# 1-Schematic_AU9560-SC-Reader.net
KiCad netlist of a schematic drawn in EasyEDA
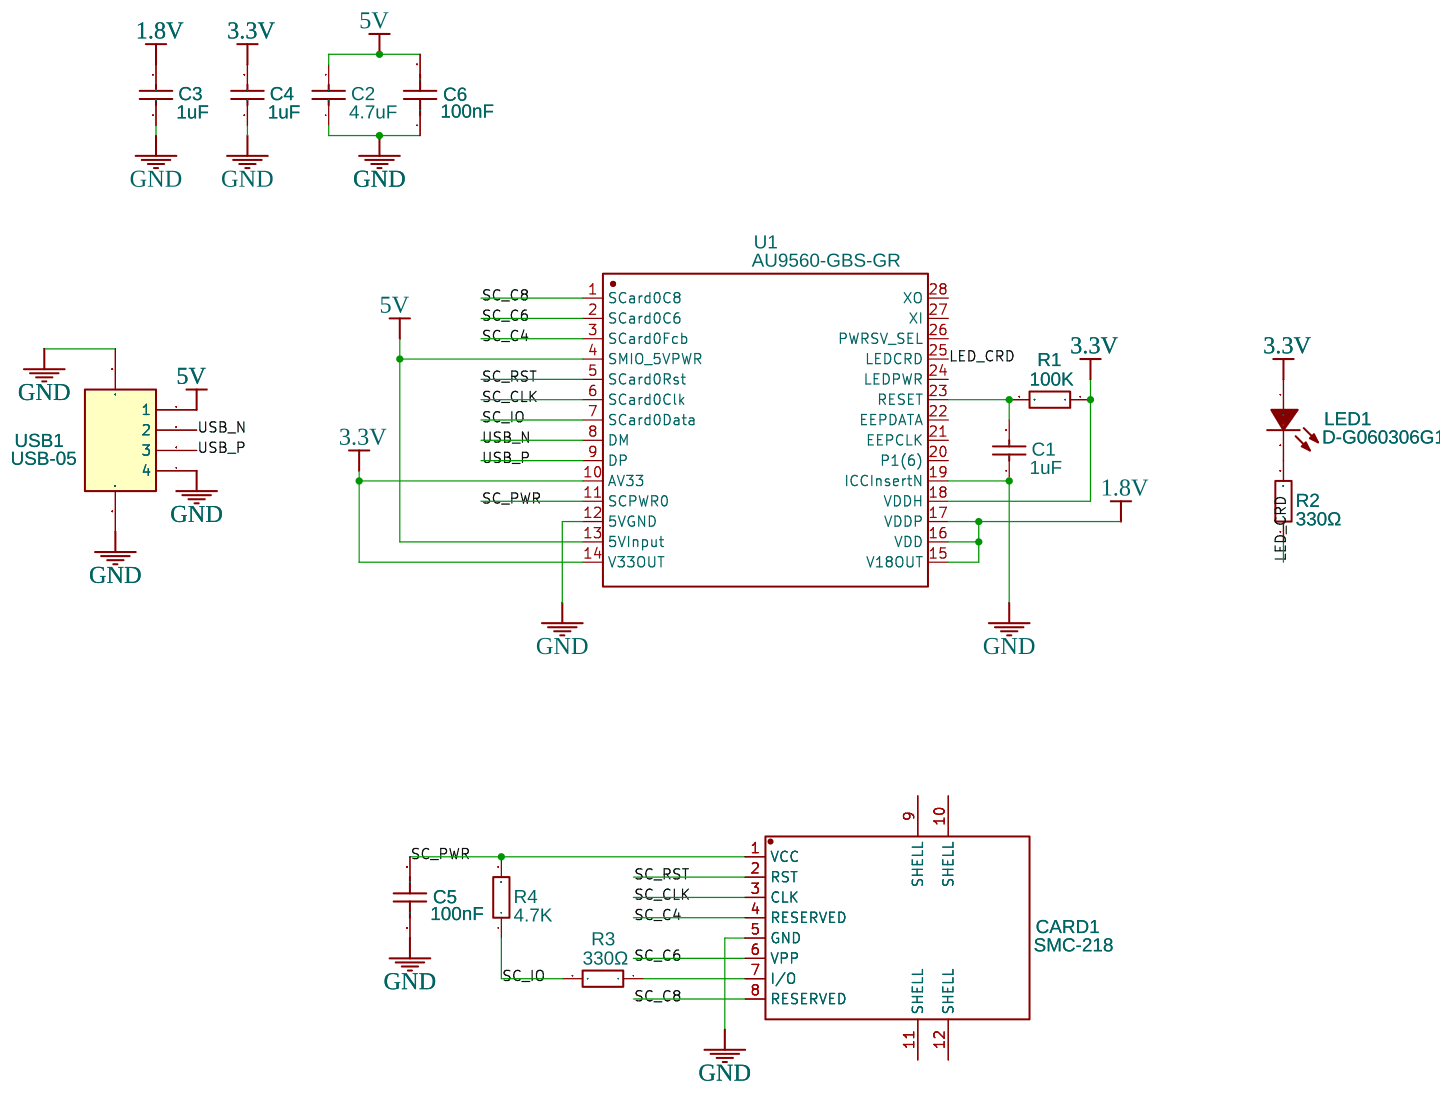
[diagram p0: schematic sheet]

(export (version "E")
  (design (tool "Eeschema 10.0.6"))
  (components
    (comp (ref "C1") (value "1uF") (libsource (lib "") (part "CL10A475KO8NNNC")))
    (comp (ref "C2") (value "4.7uF") (libsource (lib "") (part "CL10A475KO8NNNC")))
    (comp (ref "C3") (value "1uF") (libsource (lib "") (part "CL10A475KO8NNNC")))
    (comp (ref "C4") (value "1uF") (libsource (lib "") (part "CL10A475KO8NNNC")))
    (comp (ref "C5") (value "100nF") (libsource (lib "") (part "CC0603KRX7R9BB104")))
    (comp (ref "C6") (value "100nF") (libsource (lib "") (part "CC0603KRX7R9BB104")))
    (comp (ref "CARD1")
      (value "SMC-218")
      (fields (field (name "BOM_Supplier Part") "C266885"))
      (libsource (lib "") (part "Unknown_60_255"))
    )
    (comp (ref "LED1")
      (value "D-G060306G1-KS2")
      (fields (field (name "BOM_Supplier Part") "C118334"))
      (libsource (lib "") (part "Unknown_255_5"))
    )
    (comp (ref "R1") (value "100K") (libsource (lib "") (part "TC0325B1002T5E")))
    (comp (ref "R2") (value "330Ω") (libsource (lib "") (part "TC0350F4701T5E_C179829")))
    (comp (ref "R3") (value "330Ω") (libsource (lib "") (part "0603WAF1210T5E")))
    (comp (ref "R4") (value "4.7K") (libsource (lib "") (part "TC0350F4701T5E_C179829")))
    (comp (ref "U1")
      (value "AU9560-GBS-GR")
      (fields (field (name "BOM_Supplier Part") "C126999"))
      (libsource (lib "") (part "Unknown_0_10"))
    )
    (comp (ref "USB1")
      (value "USB-05")
      (fields (field (name "BOM_Supplier Part") "C112454"))
      (libsource (lib "") (part "Unknown_-305_15"))
    )
  )
  (nets
    (net (code "1") (name "/LED_CRD") (class "Default")
      (node (ref "R2") (pin "1") (pinfunction "1_1") (pintype "unspecified"))
      (node (ref "U1") (pin "25") (pinfunction "LEDCRD_25") (pintype "unspecified"))
    )
    (net (code "2") (name "/SC_C4") (class "Default")
      (node (ref "CARD1") (pin "4") (pinfunction "RESERVED_4") (pintype "unspecified"))
      (node (ref "U1") (pin "3") (pinfunction "SCard0Fcb_3") (pintype "unspecified"))
    )
    (net (code "3") (name "/SC_C6") (class "Default")
      (node (ref "CARD1") (pin "6") (pinfunction "VPP_6") (pintype "unspecified"))
      (node (ref "U1") (pin "2") (pinfunction "SCard0C6_2") (pintype "unspecified"))
    )
    (net (code "4") (name "/SC_C8") (class "Default")
      (node (ref "CARD1") (pin "8") (pinfunction "RESERVED_8") (pintype "unspecified"))
      (node (ref "U1") (pin "1") (pinfunction "SCard0C8_1") (pintype "unspecified"))
    )
    (net (code "5") (name "/SC_CLK") (class "Default")
      (node (ref "CARD1") (pin "3") (pinfunction "CLK_3") (pintype "unspecified"))
      (node (ref "U1") (pin "6") (pinfunction "SCard0Clk_6") (pintype "unspecified"))
    )
    (net (code "6") (name "/SC_IO") (class "Default")
      (node (ref "R3") (pin "2") (pinfunction "2_2") (pintype "input"))
      (node (ref "R4") (pin "1") (pinfunction "1_1") (pintype "unspecified"))
      (node (ref "U1") (pin "7") (pinfunction "SCard0Data_7") (pintype "unspecified"))
    )
    (net (code "7") (name "/SC_PWR") (class "Default")
      (node (ref "C5") (pin "2") (pinfunction "2_2") (pintype "unspecified"))
      (node (ref "CARD1") (pin "1") (pinfunction "VCC_1") (pintype "unspecified"))
      (node (ref "R4") (pin "2") (pinfunction "2_2") (pintype "unspecified"))
      (node (ref "U1") (pin "11") (pinfunction "SCPWR0_11") (pintype "unspecified"))
    )
    (net (code "8") (name "/SC_RST") (class "Default")
      (node (ref "CARD1") (pin "2") (pinfunction "RST_2") (pintype "unspecified"))
      (node (ref "U1") (pin "5") (pinfunction "SCard0Rst_5") (pintype "unspecified"))
    )
    (net (code "9") (name "/USB_N") (class "Default")
      (node (ref "U1") (pin "8") (pinfunction "DM_8") (pintype "unspecified"))
      (node (ref "USB1") (pin "2") (pinfunction "2_2") (pintype "input"))
    )
    (net (code "10") (name "/USB_P") (class "Default")
      (node (ref "U1") (pin "9") (pinfunction "DP_9") (pintype "unspecified"))
      (node (ref "USB1") (pin "3") (pinfunction "3_3") (pintype "input"))
    )
    (net (code "11") (name "1.8V") (class "Default")
      (node (ref "C3") (pin "2") (pinfunction "2_2") (pintype "input"))
      (node (ref "U1") (pin "15") (pinfunction "V18OUT_15") (pintype "unspecified"))
      (node (ref "U1") (pin "16") (pinfunction "VDD_16") (pintype "unspecified"))
      (node (ref "U1") (pin "17") (pinfunction "VDDP_17") (pintype "unspecified"))
    )
    (net (code "12") (name "3.3V") (class "Default")
      (node (ref "C4") (pin "2") (pinfunction "2_2") (pintype "input"))
      (node (ref "LED1") (pin "1") (pinfunction "A_1") (pintype "unspecified"))
      (node (ref "R1") (pin "1") (pinfunction "1_1") (pintype "input"))
      (node (ref "U1") (pin "10") (pinfunction "AV33_10") (pintype "unspecified"))
      (node (ref "U1") (pin "14") (pinfunction "V33OUT_14") (pintype "unspecified"))
      (node (ref "U1") (pin "18") (pinfunction "VDDH_18") (pintype "unspecified"))
    )
    (net (code "13") (name "5V") (class "Default")
      (node (ref "C2") (pin "2") (pinfunction "2_2") (pintype "input"))
      (node (ref "C6") (pin "2") (pinfunction "2_2") (pintype "unspecified"))
      (node (ref "U1") (pin "13") (pinfunction "5VInput_13") (pintype "unspecified"))
      (node (ref "U1") (pin "4") (pinfunction "SMIO_5VPWR_4") (pintype "unspecified"))
      (node (ref "USB1") (pin "1") (pinfunction "1_1") (pintype "input"))
    )
    (net (code "14") (name "GND") (class "Default")
      (node (ref "C1") (pin "1") (pinfunction "1_1") (pintype "input"))
      (node (ref "C2") (pin "1") (pinfunction "1_1") (pintype "input"))
      (node (ref "C3") (pin "1") (pinfunction "1_1") (pintype "input"))
      (node (ref "C4") (pin "1") (pinfunction "1_1") (pintype "input"))
      (node (ref "C5") (pin "1") (pinfunction "1_1") (pintype "unspecified"))
      (node (ref "C6") (pin "1") (pinfunction "1_1") (pintype "unspecified"))
      (node (ref "CARD1") (pin "5") (pinfunction "GND_5") (pintype "unspecified"))
      (node (ref "U1") (pin "12") (pinfunction "5VGND_12") (pintype "unspecified"))
      (node (ref "U1") (pin "19") (pinfunction "ICCInsertN_19") (pintype "unspecified"))
      (node (ref "USB1") (pin "0") (pinfunction "0_0") (pintype "unspecified"))
      (node (ref "USB1") (pin "4") (pinfunction "4_4") (pintype "input"))
      (node (ref "USB1") (pin "6") (pinfunction "6_6") (pintype "unspecified"))
    )
    (net (code "15") (name "Net-(CARD1-I{slash}O)") (class "Default")
      (node (ref "CARD1") (pin "7") (pinfunction "I/O_7") (pintype "unspecified"))
      (node (ref "R3") (pin "1") (pinfunction "1_1") (pintype "input"))
    )
    (net (code "16") (name "Net-(LED1-K)") (class "Default")
      (node (ref "LED1") (pin "2") (pinfunction "K_2") (pintype "unspecified"))
      (node (ref "R2") (pin "2") (pinfunction "2_2") (pintype "unspecified"))
    )
    (net (code "17") (name "Net-(U1-RESET)") (class "Default")
      (node (ref "C1") (pin "2") (pinfunction "2_2") (pintype "input"))
      (node (ref "R1") (pin "2") (pinfunction "2_2") (pintype "input"))
      (node (ref "U1") (pin "23") (pinfunction "RESET_23") (pintype "unspecified"))
    )
    (net (code "18") (name "unconnected-(CARD1-SHELL-Pad9)") (class "Default")
      (node (ref "CARD1") (pin "9") (pinfunction "SHELL_9") (pintype "unspecified"))
    )
    (net (code "19") (name "unconnected-(CARD1-SHELL-Pad10)") (class "Default")
      (node (ref "CARD1") (pin "10") (pinfunction "SHELL_10") (pintype "unspecified"))
    )
    (net (code "20") (name "unconnected-(CARD1-SHELL-Pad11)") (class "Default")
      (node (ref "CARD1") (pin "11") (pinfunction "SHELL_11") (pintype "unspecified"))
    )
    (net (code "21") (name "unconnected-(CARD1-SHELL-Pad12)") (class "Default")
      (node (ref "CARD1") (pin "12") (pinfunction "SHELL_12") (pintype "unspecified"))
    )
    (net (code "22") (name "unconnected-(U1-EEPCLK-Pad21)") (class "Default")
      (node (ref "U1") (pin "21") (pinfunction "EEPCLK_21") (pintype "unspecified"))
    )
    (net (code "23") (name "unconnected-(U1-EEPDATA-Pad22)") (class "Default")
      (node (ref "U1") (pin "22") (pinfunction "EEPDATA_22") (pintype "unspecified"))
    )
    (net (code "24") (name "unconnected-(U1-LEDPWR-Pad24)") (class "Default")
      (node (ref "U1") (pin "24") (pinfunction "LEDPWR_24") (pintype "unspecified"))
    )
    (net (code "25") (name "unconnected-(U1-P1(6)-Pad20)") (class "Default")
      (node (ref "U1") (pin "20") (pinfunction "P1(6)_20") (pintype "unspecified"))
    )
    (net (code "26") (name "unconnected-(U1-PWRSV_SEL-Pad26)") (class "Default")
      (node (ref "U1") (pin "26") (pinfunction "PWRSV_SEL_26") (pintype "unspecified"))
    )
    (net (code "27") (name "unconnected-(U1-XI-Pad27)") (class "Default")
      (node (ref "U1") (pin "27") (pinfunction "XI_27") (pintype "unspecified"))
    )
    (net (code "28") (name "unconnected-(U1-XO-Pad28)") (class "Default")
      (node (ref "U1") (pin "28") (pinfunction "XO_28") (pintype "unspecified"))
    )
  )
)
